# hitmouse.net
KiCad netlist of a schematic drawn in Altium Designer
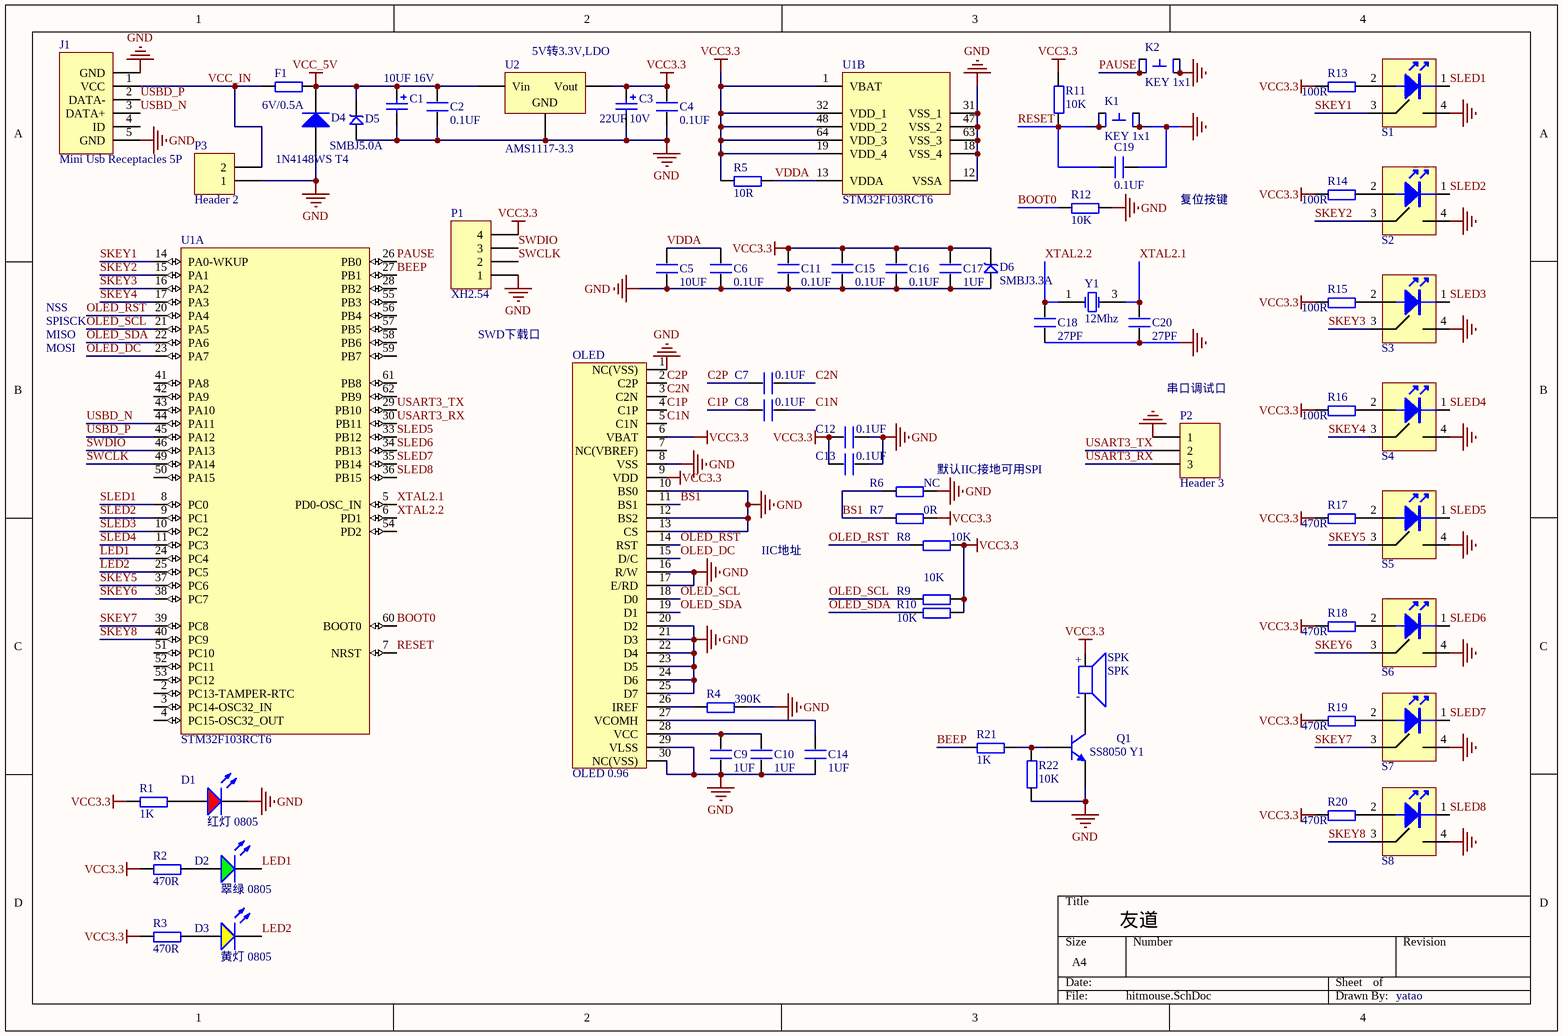
[diagram p0: hitmouse.SchDoc]

(export (version "E")
  (design (tool "Eeschema 10.0.6"))
  (components
    (comp (ref "*")
      (value "LOGO")
      (footprint "LOGO-14MM")
      (description "YOODAO-LOGO不焊接")
      (libsource (lib "yoodao") (part "LOGO"))
    )
    (comp (ref "C1")
      (value "10UF 16V")
      (footprint "CASE-A_3216")
      (description "钽电容A")
      (libsource (lib "yoodao") (part "C3216,A型钽电容"))
    )
    (comp (ref "C2")
      (value "0.1UF")
      (footprint "0805_C")
      (description "0805电容")
      (libsource (lib "") (part "C0805_1"))
    )
    (comp (ref "C3")
      (value "22UF 10V")
      (footprint "CASE-A_3216")
      (description "钽电容A")
      (libsource (lib "yoodao") (part "C3216,A型钽电容"))
    )
    (comp (ref "C4")
      (value "0.1UF")
      (footprint "0805_C")
      (description "0805电容")
      (libsource (lib "") (part "C0805_1"))
    )
    (comp (ref "C5")
      (value "10UF")
      (footprint "0805_C")
      (description "0805电容")
      (libsource (lib "yoodao") (part "C0805"))
    )
    (comp (ref "C6")
      (value "0.1UF")
      (footprint "0805_C")
      (description "0805电容")
      (libsource (lib "yoodao") (part "C0805"))
    )
    (comp (ref "C7")
      (value "0.1UF")
      (footprint "0805_C")
      (description "0805电容")
      (libsource (lib "yoodao") (part "C0805"))
    )
    (comp (ref "C8")
      (value "0.1UF")
      (footprint "0805_C")
      (description "0805电容")
      (libsource (lib "yoodao") (part "C0805"))
    )
    (comp (ref "C9")
      (value "1UF")
      (footprint "0805_C")
      (description "0805电容")
      (libsource (lib "yoodao") (part "C0805"))
    )
    (comp (ref "C10")
      (value "1UF")
      (footprint "0805_C")
      (description "0805电容")
      (libsource (lib "yoodao") (part "C0805"))
    )
    (comp (ref "C11")
      (value "0.1UF")
      (footprint "0805_C")
      (description "0805电容")
      (libsource (lib "yoodao") (part "C0805"))
    )
    (comp (ref "C12")
      (value "0.1UF")
      (footprint "0805_C")
      (description "0805电容")
      (libsource (lib "yoodao") (part "C0805"))
    )
    (comp (ref "C13")
      (value "0.1UF")
      (footprint "0805_C")
      (description "0805电容")
      (libsource (lib "yoodao") (part "C0805"))
    )
    (comp (ref "C14")
      (value "1UF")
      (footprint "0805_C")
      (description "0805电容")
      (libsource (lib "yoodao") (part "C0805"))
    )
    (comp (ref "C15")
      (value "0.1UF")
      (footprint "0805_C")
      (description "0805电容")
      (libsource (lib "yoodao") (part "C0805"))
    )
    (comp (ref "C16")
      (value "0.1UF")
      (footprint "0805_C")
      (description "0805电容")
      (libsource (lib "yoodao") (part "C0805"))
    )
    (comp (ref "C17")
      (value "1UF")
      (footprint "0805_C")
      (description "0805电容")
      (libsource (lib "yoodao") (part "C0805"))
    )
    (comp (ref "C18")
      (value "27PF")
      (footprint "0805_C")
      (description "0805电容")
      (libsource (lib "") (part "C0805_1"))
    )
    (comp (ref "C19")
      (value "0.1UF")
      (footprint "0805_C")
      (description "0805电容")
      (libsource (lib "") (part "C0805_1"))
    )
    (comp (ref "C20")
      (value "27PF")
      (footprint "0805_C")
      (description "0805电容")
      (libsource (lib "") (part "C0805_1"))
    )
    (comp (ref "D1")
      (value "红灯 0805")
      (footprint "0805_LED_S1")
      (description "发光二极管")
      (libsource (lib "yoodao") (part "0805 红灯"))
    )
    (comp (ref "D2")
      (value "翠绿 0805")
      (footprint "0805_LED_S1")
      (description "发光二极管")
      (libsource (lib "yoodao") (part "0805 翠绿"))
    )
    (comp (ref "D3")
      (value "黄灯 0805")
      (footprint "0805_LED_S1")
      (description "发光二极管")
      (libsource (lib "yoodao") (part "0805 黄灯"))
    )
    (comp (ref "D4")
      (value "1N4148WS T4")
      (footprint "SOD-323")
      (description "二极管")
      (libsource (lib "yoodao") (part "SOD-323 1N4148WS T4"))
    )
    (comp (ref "D5")
      (value "SMBJ5.0A")
      (footprint "SMBJ")
      (description "TVS")
      (libsource (lib "yoodao") (part "SMBJ"))
    )
    (comp (ref "D6")
      (value "SMBJ3.3A")
      (footprint "SMBJ")
      (description "TVS")
      (libsource (lib "yoodao") (part "SMBJ"))
    )
    (comp (ref "F1")
      (value "6V/0.5A")
      (footprint "0805_R")
      (description "0805贴片自恢复保险丝")
      (libsource (lib "yoodao") (part "R0805"))
    )
    (comp (ref "J1")
      (value "Mini Usb Receptacles 5P")
      (footprint "USB Micro MUP U513 F")
      (description "Micro USB 母座 5P 全贴有柱")
      (libsource (lib "yoodao") (part "USB Mini"))
    )
    (comp (ref "K1")
      (value "KEY 1x1")
      (footprint "BUT 6mm SMT")
      (description "贴片轻触按键6*6*5")
      (libsource (lib "yoodao") (part "KEY 1x1"))
    )
    (comp (ref "K2")
      (value "KEY 1x1")
      (footprint "BUT 6mm SMT")
      (description "贴片轻触按键6*6*5")
      (libsource (lib "yoodao") (part "KEY 1x1"))
    )
    (comp (ref "OLED")
      (value "OLED 0.96")
      (footprint "0.96_OLED")
      (description "0.96寸OLED贴片")
      (libsource (lib "yoodao") (part "OLED"))
    )
    (comp (ref "P1")
      (value "XH2.54")
      (footprint "XH2.54-LI-4P")
      (description "XH2.54 直/弯 带围墙")
      (fields (field (name "PUBLISHER") "Altium Limited"))
      (libsource (lib "yoodao") (part "XH2.54"))
    )
    (comp (ref "P2")
      (value "Header 3")
      (footprint "HDR1X3")
      (description "2.54直针")
      (fields (field (name "PUBLISHER") "Altium Limited"))
      (libsource (lib "yoodao") (part "Header 3"))
    )
    (comp (ref "P3")
      (value "Header 2")
      (footprint "HDR1X2")
      (description "Header, 2-Pin")
      (fields (field (name "PUBLISHER") "Altium Limited"))
      (libsource (lib "yoodao") (part "Header 2"))
    )
    (comp (ref "Q1")
      (value "SS8050 Y1")
      (footprint "SOT-23(SOT-23-3)")
      (description "NPN三极管SOT23")
      (libsource (lib "yoodao") (part "NPN"))
    )
    (comp (ref "R1")
      (value "1K")
      (footprint "0805_R")
      (description "0805贴片电阻")
      (libsource (lib "yoodao") (part "R0805"))
    )
    (comp (ref "R2")
      (value "470R")
      (footprint "0805_R")
      (description "0805贴片电阻")
      (libsource (lib "yoodao") (part "R0805"))
    )
    (comp (ref "R3")
      (value "470R")
      (footprint "0805_R")
      (description "0805贴片电阻")
      (libsource (lib "yoodao") (part "R0805"))
    )
    (comp (ref "R4")
      (value "390K")
      (footprint "0805_R")
      (description "0805贴片电阻")
      (libsource (lib "yoodao") (part "R0805"))
    )
    (comp (ref "R5")
      (value "10R")
      (footprint "0805_R")
      (description "0805贴片电阻")
      (libsource (lib "yoodao") (part "R0805"))
    )
    (comp (ref "R6")
      (value "NC")
      (footprint "0805_R")
      (description "0805贴片电阻")
      (libsource (lib "yoodao") (part "R0805"))
    )
    (comp (ref "R7")
      (value "0R")
      (footprint "0805_R")
      (description "0805贴片电阻")
      (libsource (lib "yoodao") (part "R0805"))
    )
    (comp (ref "R8")
      (value "10K")
      (footprint "0805_R")
      (description "0805贴片电阻")
      (libsource (lib "yoodao") (part "R0805"))
    )
    (comp (ref "R9")
      (value "10K")
      (footprint "0805_R")
      (description "0805贴片电阻")
      (libsource (lib "yoodao") (part "R0805"))
    )
    (comp (ref "R10")
      (value "10K")
      (footprint "0805_R")
      (description "0805贴片电阻")
      (libsource (lib "yoodao") (part "R0805"))
    )
    (comp (ref "R11")
      (value "10K")
      (footprint "0805_R")
      (description "0805贴片电阻")
      (libsource (lib "yoodao") (part "R0805"))
    )
    (comp (ref "R12")
      (value "10K")
      (footprint "0805_R")
      (description "0805贴片电阻")
      (libsource (lib "yoodao") (part "R0805"))
    )
    (comp (ref "R13")
      (value "100R")
      (footprint "0805_R")
      (description "0805贴片电阻")
      (libsource (lib "yoodao") (part "R0805"))
    )
    (comp (ref "R14")
      (value "100R")
      (footprint "0805_R")
      (description "0805贴片电阻")
      (libsource (lib "yoodao") (part "R0805"))
    )
    (comp (ref "R15")
      (value "100R")
      (footprint "0805_R")
      (description "0805贴片电阻")
      (libsource (lib "yoodao") (part "R0805"))
    )
    (comp (ref "R16")
      (value "100R")
      (footprint "0805_R")
      (description "0805贴片电阻")
      (libsource (lib "yoodao") (part "R0805"))
    )
    (comp (ref "R17")
      (value "470R")
      (footprint "0805_R")
      (description "0805贴片电阻")
      (libsource (lib "yoodao") (part "R0805"))
    )
    (comp (ref "R18")
      (value "470R")
      (footprint "0805_R")
      (description "0805贴片电阻")
      (libsource (lib "yoodao") (part "R0805"))
    )
    (comp (ref "R19")
      (value "470R")
      (footprint "0805_R")
      (description "0805贴片电阻")
      (libsource (lib "yoodao") (part "R0805"))
    )
    (comp (ref "R20")
      (value "470R")
      (footprint "0805_R")
      (description "0805贴片电阻")
      (libsource (lib "yoodao") (part "R0805"))
    )
    (comp (ref "R21")
      (value "1K")
      (footprint "0805_R")
      (description "0805贴片电阻")
      (libsource (lib "yoodao") (part "R0805"))
    )
    (comp (ref "R22")
      (value "10K")
      (footprint "0805_R")
      (description "0805贴片电阻")
      (libsource (lib "yoodao") (part "R0805"))
    )
    (comp (ref "S1")
      (value "12X12轻触带灯开关")
      (footprint "TSG010")
      (description "12X12按键带灯直插")
      (libsource (lib "yoodao") (part "LED开关12X12"))
    )
    (comp (ref "S2")
      (value "12X12轻触带灯开关")
      (footprint "TSG010")
      (description "12X12按键带灯直插")
      (libsource (lib "yoodao") (part "LED开关12X12"))
    )
    (comp (ref "S3")
      (value "12X12轻触带灯开关")
      (footprint "TSG010")
      (description "12X12按键带灯直插")
      (libsource (lib "yoodao") (part "LED开关12X12"))
    )
    (comp (ref "S4")
      (value "12X12轻触带灯开关")
      (footprint "TSG010")
      (description "12X12按键带灯直插")
      (libsource (lib "yoodao") (part "LED开关12X12"))
    )
    (comp (ref "S5")
      (value "12X12轻触带灯开关")
      (footprint "TSG010")
      (description "12X12按键带灯直插")
      (libsource (lib "yoodao") (part "LED开关12X12"))
    )
    (comp (ref "S6")
      (value "12X12轻触带灯开关")
      (footprint "TSG010")
      (description "12X12按键带灯直插")
      (libsource (lib "yoodao") (part "LED开关12X12"))
    )
    (comp (ref "S7")
      (value "12X12轻触带灯开关")
      (footprint "TSG010")
      (description "12X12按键带灯直插")
      (libsource (lib "yoodao") (part "LED开关12X12"))
    )
    (comp (ref "S8")
      (value "12X12轻触带灯开关")
      (footprint "TSG010")
      (description "12X12按键带灯直插")
      (libsource (lib "yoodao") (part "LED开关12X12"))
    )
    (comp (ref "SPK")
      (value "SPK")
      (footprint "SPAKER F12")
      (description "3.3V无源蜂鸣器，脚距7mm")
      (libsource (lib "yoodao") (part "SPK"))
    )
    (comp (ref "U1")
      (value "STM32F103RCT6")
      (footprint "LQFP-64_10x10x05P")
      (description "ARM")
      (libsource (lib "yoodao") (part "STM32F103RCT6"))
    )
    (comp (ref "U2")
      (value "AMS1117-3.3")
      (footprint "SOT-223")
      (description "低压差线性稳压(LDO)")
      (libsource (lib "yoodao") (part "SOT-223 AMS1117-3.3"))
    )
    (comp (ref "Y1")
      (value "12Mhz")
      (footprint "SMD-3225_4P")
      (description "2P无源贴片晶振3225")
      (libsource (lib "yoodao") (part "XTAL-3225_4P"))
    )
    (comp (ref "yatao")
      (value "NC")
      (footprint "Y-LOGO-8")
      (description "LOGO，不焊接")
      (libsource (lib "yoodao") (part "Yatao"))
    )
  )
  (nets
    (net (code "1") (name "/BEEP") (class "Default")
      (node (ref "R21") (pin "1") (pintype "passive"))
      (node (ref "U1") (pin "27") (pinfunction "PB1_27") (pintype "bidirectional"))
    )
    (net (code "2") (name "/BOOT0") (class "Default")
      (node (ref "R12") (pin "1") (pintype "passive"))
      (node (ref "U1") (pin "60") (pinfunction "BOOT0_60") (pintype "bidirectional"))
    )
    (net (code "3") (name "/BS1") (class "Default")
      (node (ref "OLED") (pin "11") (pinfunction "BS1_11") (pintype "passive"))
      (node (ref "R6") (pin "1") (pintype "passive"))
      (node (ref "R7") (pin "1") (pintype "passive"))
    )
    (net (code "4") (name "/C1N") (class "Default")
      (node (ref "C8") (pin "1") (pintype "passive"))
      (node (ref "OLED") (pin "5") (pinfunction "C1N_5") (pintype "passive"))
    )
    (net (code "5") (name "/C1P") (class "Default")
      (node (ref "C8") (pin "2") (pintype "passive"))
      (node (ref "OLED") (pin "4") (pinfunction "C1P_4") (pintype "passive"))
    )
    (net (code "6") (name "/C2N") (class "Default")
      (node (ref "C7") (pin "1") (pintype "passive"))
      (node (ref "OLED") (pin "3") (pinfunction "C2N_3") (pintype "passive"))
    )
    (net (code "7") (name "/C2P") (class "Default")
      (node (ref "C7") (pin "2") (pintype "passive"))
      (node (ref "OLED") (pin "2") (pinfunction "C2P_2") (pintype "passive"))
    )
    (net (code "8") (name "/LED1") (class "Default")
      (node (ref "D2") (pin "K") (pinfunction "K_K") (pintype "passive"))
      (node (ref "U1") (pin "24") (pinfunction "PC4_24") (pintype "bidirectional"))
    )
    (net (code "9") (name "/LED2") (class "Default")
      (node (ref "D3") (pin "K") (pinfunction "K_K") (pintype "passive"))
      (node (ref "U1") (pin "25") (pinfunction "PC5_25") (pintype "bidirectional"))
    )
    (net (code "10") (name "/OLED_DC") (class "Default")
      (node (ref "OLED") (pin "15") (pinfunction "D/C_15") (pintype "passive"))
      (node (ref "U1") (pin "23") (pinfunction "PA7_23") (pintype "bidirectional"))
    )
    (net (code "11") (name "/OLED_RST") (class "Default")
      (node (ref "OLED") (pin "14") (pinfunction "RST_14") (pintype "passive"))
      (node (ref "R8") (pin "1") (pintype "passive"))
      (node (ref "U1") (pin "20") (pinfunction "PA4_20") (pintype "bidirectional"))
    )
    (net (code "12") (name "/OLED_SCL") (class "Default")
      (node (ref "OLED") (pin "18") (pinfunction "D0_18") (pintype "passive"))
      (node (ref "R9") (pin "1") (pintype "passive"))
      (node (ref "U1") (pin "21") (pinfunction "PA5_21") (pintype "bidirectional"))
    )
    (net (code "13") (name "/OLED_SDA") (class "Default")
      (node (ref "OLED") (pin "19") (pinfunction "D1_19") (pintype "passive"))
      (node (ref "R10") (pin "1") (pintype "passive"))
      (node (ref "U1") (pin "22") (pinfunction "PA6_22") (pintype "bidirectional"))
    )
    (net (code "14") (name "/PAUSE") (class "Default")
      (node (ref "K2") (pin "1") (pinfunction "1_1") (pintype "passive"))
      (node (ref "K2") (pin "2") (pinfunction "2_2") (pintype "passive"))
      (node (ref "U1") (pin "26") (pinfunction "PB0_26") (pintype "bidirectional"))
    )
    (net (code "15") (name "/RESET") (class "Default")
      (node (ref "C19") (pin "2") (pintype "passive"))
      (node (ref "K1") (pin "1") (pinfunction "1_1") (pintype "passive"))
      (node (ref "K1") (pin "2") (pinfunction "2_2") (pintype "passive"))
      (node (ref "R11") (pin "1") (pintype "passive"))
      (node (ref "U1") (pin "7") (pinfunction "NRST_7") (pintype "bidirectional"))
    )
    (net (code "16") (name "/SKEY1") (class "Default")
      (node (ref "S1") (pin "3") (pinfunction "3_3") (pintype "passive"))
      (node (ref "U1") (pin "14") (pinfunction "PA0-WKUP_14") (pintype "bidirectional"))
    )
    (net (code "17") (name "/SKEY2") (class "Default")
      (node (ref "S2") (pin "3") (pinfunction "3_3") (pintype "passive"))
      (node (ref "U1") (pin "15") (pinfunction "PA1_15") (pintype "bidirectional"))
    )
    (net (code "18") (name "/SKEY3") (class "Default")
      (node (ref "S3") (pin "3") (pinfunction "3_3") (pintype "passive"))
      (node (ref "U1") (pin "16") (pinfunction "PA2_16") (pintype "bidirectional"))
    )
    (net (code "19") (name "/SKEY4") (class "Default")
      (node (ref "S4") (pin "3") (pinfunction "3_3") (pintype "passive"))
      (node (ref "U1") (pin "17") (pinfunction "PA3_17") (pintype "bidirectional"))
    )
    (net (code "20") (name "/SKEY5") (class "Default")
      (node (ref "S5") (pin "3") (pinfunction "3_3") (pintype "passive"))
      (node (ref "U1") (pin "37") (pinfunction "PC6_37") (pintype "bidirectional"))
    )
    (net (code "21") (name "/SKEY6") (class "Default")
      (node (ref "S6") (pin "3") (pinfunction "3_3") (pintype "passive"))
      (node (ref "U1") (pin "38") (pinfunction "PC7_38") (pintype "bidirectional"))
    )
    (net (code "22") (name "/SKEY7") (class "Default")
      (node (ref "S7") (pin "3") (pinfunction "3_3") (pintype "passive"))
      (node (ref "U1") (pin "39") (pinfunction "PC8_39") (pintype "bidirectional"))
    )
    (net (code "23") (name "/SKEY8") (class "Default")
      (node (ref "S8") (pin "3") (pinfunction "3_3") (pintype "passive"))
      (node (ref "U1") (pin "40") (pinfunction "PC9_40") (pintype "bidirectional"))
    )
    (net (code "24") (name "/SLED1") (class "Default")
      (node (ref "S1") (pin "1") (pinfunction "1_1") (pintype "passive"))
      (node (ref "U1") (pin "8") (pinfunction "PC0_8") (pintype "bidirectional"))
    )
    (net (code "25") (name "/SLED2") (class "Default")
      (node (ref "S2") (pin "1") (pinfunction "1_1") (pintype "passive"))
      (node (ref "U1") (pin "9") (pinfunction "PC1_9") (pintype "bidirectional"))
    )
    (net (code "26") (name "/SLED3") (class "Default")
      (node (ref "S3") (pin "1") (pinfunction "1_1") (pintype "passive"))
      (node (ref "U1") (pin "10") (pinfunction "PC2_10") (pintype "bidirectional"))
    )
    (net (code "27") (name "/SLED4") (class "Default")
      (node (ref "S4") (pin "1") (pinfunction "1_1") (pintype "passive"))
      (node (ref "U1") (pin "11") (pinfunction "PC3_11") (pintype "bidirectional"))
    )
    (net (code "28") (name "/SLED5") (class "Default")
      (node (ref "S5") (pin "1") (pinfunction "1_1") (pintype "passive"))
      (node (ref "U1") (pin "33") (pinfunction "PB12_33") (pintype "bidirectional"))
    )
    (net (code "29") (name "/SLED6") (class "Default")
      (node (ref "S6") (pin "1") (pinfunction "1_1") (pintype "passive"))
      (node (ref "U1") (pin "34") (pinfunction "PB13_34") (pintype "bidirectional"))
    )
    (net (code "30") (name "/SLED7") (class "Default")
      (node (ref "S7") (pin "1") (pinfunction "1_1") (pintype "passive"))
      (node (ref "U1") (pin "35") (pinfunction "PB14_35") (pintype "bidirectional"))
    )
    (net (code "31") (name "/SLED8") (class "Default")
      (node (ref "S8") (pin "1") (pinfunction "1_1") (pintype "passive"))
      (node (ref "U1") (pin "36") (pinfunction "PB15_36") (pintype "bidirectional"))
    )
    (net (code "32") (name "/SWCLK") (class "Default")
      (node (ref "P1") (pin "2") (pinfunction "2_2") (pintype "passive"))
      (node (ref "U1") (pin "49") (pinfunction "PA14_49") (pintype "bidirectional"))
    )
    (net (code "33") (name "/SWDIO") (class "Default")
      (node (ref "P1") (pin "3") (pinfunction "3_3") (pintype "passive"))
      (node (ref "U1") (pin "46") (pinfunction "PA13_46") (pintype "bidirectional"))
    )
    (net (code "34") (name "/USART3_RX") (class "Default")
      (node (ref "P2") (pin "3") (pinfunction "3_3") (pintype "passive"))
      (node (ref "U1") (pin "30") (pinfunction "PB11_30") (pintype "bidirectional"))
    )
    (net (code "35") (name "/USART3_TX") (class "Default")
      (node (ref "P2") (pin "2") (pinfunction "2_2") (pintype "passive"))
      (node (ref "U1") (pin "29") (pinfunction "PB10_29") (pintype "bidirectional"))
    )
    (net (code "36") (name "/USBD_N") (class "Default")
      (node (ref "J1") (pin "3") (pinfunction "DATA+_3") (pintype "passive"))
      (node (ref "U1") (pin "44") (pinfunction "PA11_44") (pintype "bidirectional"))
    )
    (net (code "37") (name "/USBD_P") (class "Default")
      (node (ref "J1") (pin "2") (pinfunction "DATA-_2") (pintype "passive"))
      (node (ref "U1") (pin "45") (pinfunction "PA12_45") (pintype "bidirectional"))
    )
    (net (code "38") (name "/VCC_IN") (class "Default")
      (node (ref "F1") (pin "1") (pintype "passive"))
      (node (ref "J1") (pin "1") (pinfunction "VCC_1") (pintype "passive"))
      (node (ref "P3") (pin "2") (pinfunction "2_2") (pintype "passive"))
    )
    (net (code "39") (name "/VDDA") (class "Default")
      (node (ref "C5") (pin "2") (pintype "passive"))
      (node (ref "C6") (pin "2") (pintype "passive"))
      (node (ref "R5") (pin "2") (pintype "passive"))
      (node (ref "U1") (pin "13") (pinfunction "VDDA_13") (pintype "power_in"))
    )
    (net (code "40") (name "/XTAL2.1") (class "Default")
      (node (ref "C20") (pin "1") (pintype "passive"))
      (node (ref "U1") (pin "5") (pinfunction "PD0-OSC_IN_5") (pintype "bidirectional"))
      (node (ref "Y1") (pin "3") (pinfunction "OSC2_3") (pintype "passive"))
    )
    (net (code "41") (name "/XTAL2.2") (class "Default")
      (node (ref "C18") (pin "1") (pintype "passive"))
      (node (ref "U1") (pin "6") (pinfunction "PD1_6") (pintype "bidirectional"))
      (node (ref "Y1") (pin "1") (pinfunction "OSC1_1") (pintype "passive"))
    )
    (net (code "42") (name "GND") (class "Default")
      (node (ref "C1") (pin "2") (pinfunction "2_2") (pintype "passive"))
      (node (ref "C10") (pin "1") (pintype "passive"))
      (node (ref "C11") (pin "1") (pintype "passive"))
      (node (ref "C12") (pin "1") (pintype "passive"))
      (node (ref "C13") (pin "1") (pintype "passive"))
      (node (ref "C14") (pin "1") (pintype "passive"))
      (node (ref "C15") (pin "1") (pintype "passive"))
      (node (ref "C16") (pin "1") (pintype "passive"))
      (node (ref "C17") (pin "1") (pintype "passive"))
      (node (ref "C18") (pin "2") (pintype "passive"))
      (node (ref "C19") (pin "1") (pintype "passive"))
      (node (ref "C2") (pin "1") (pintype "passive"))
      (node (ref "C20") (pin "2") (pintype "passive"))
      (node (ref "C3") (pin "2") (pinfunction "2_2") (pintype "passive"))
      (node (ref "C4") (pin "1") (pintype "passive"))
      (node (ref "C5") (pin "1") (pintype "passive"))
      (node (ref "C6") (pin "1") (pintype "passive"))
      (node (ref "C9") (pin "1") (pintype "passive"))
      (node (ref "D1") (pin "K") (pinfunction "K_K") (pintype "passive"))
      (node (ref "D4") (pin "1") (pinfunction "A_1") (pintype "passive"))
      (node (ref "D5") (pin "1") (pintype "passive"))
      (node (ref "D6") (pin "1") (pintype "passive"))
      (node (ref "J1") (pin "0") (pinfunction "GND_0") (pintype "passive"))
      (node (ref "J1") (pin "5") (pinfunction "GND_5") (pintype "passive"))
      (node (ref "K1") (pin "3") (pinfunction "3_3") (pintype "passive"))
      (node (ref "K1") (pin "4") (pinfunction "4_4") (pintype "passive"))
      (node (ref "K2") (pin "3") (pinfunction "3_3") (pintype "passive"))
      (node (ref "K2") (pin "4") (pinfunction "4_4") (pintype "passive"))
      (node (ref "OLED") (pin "1") (pinfunction "NC(VSS)_1") (pintype "passive"))
      (node (ref "OLED") (pin "10") (pinfunction "BS0_10") (pintype "passive"))
      (node (ref "OLED") (pin "12") (pinfunction "BS2_12") (pintype "passive"))
      (node (ref "OLED") (pin "13") (pinfunction "CS_13") (pintype "passive"))
      (node (ref "OLED") (pin "16") (pinfunction "R/W_16") (pintype "passive"))
      (node (ref "OLED") (pin "17") (pinfunction "E/RD_17") (pintype "passive"))
      (node (ref "OLED") (pin "20") (pinfunction "D2_20") (pintype "passive"))
      (node (ref "OLED") (pin "21") (pinfunction "D3_21") (pintype "passive"))
      (node (ref "OLED") (pin "22") (pinfunction "D4_22") (pintype "passive"))
      (node (ref "OLED") (pin "23") (pinfunction "D5_23") (pintype "passive"))
      (node (ref "OLED") (pin "24") (pinfunction "D6_24") (pintype "passive"))
      (node (ref "OLED") (pin "25") (pinfunction "D7_25") (pintype "passive"))
      (node (ref "OLED") (pin "29") (pinfunction "VLSS_29") (pintype "passive"))
      (node (ref "OLED") (pin "30") (pinfunction "NC(VSS)_30") (pintype "passive"))
      (node (ref "OLED") (pin "8") (pinfunction "VSS_8") (pintype "passive"))
      (node (ref "P1") (pin "1") (pinfunction "1_1") (pintype "passive"))
      (node (ref "P2") (pin "1") (pinfunction "1_1") (pintype "passive"))
      (node (ref "P3") (pin "1") (pinfunction "1_1") (pintype "passive"))
      (node (ref "Q1") (pin "2") (pinfunction "E_2") (pintype "passive"))
      (node (ref "R12") (pin "2") (pintype "passive"))
      (node (ref "R22") (pin "1") (pintype "passive"))
      (node (ref "R4") (pin "2") (pintype "passive"))
      (node (ref "R6") (pin "2") (pintype "passive"))
      (node (ref "S1") (pin "4") (pinfunction "4_4") (pintype "passive"))
      (node (ref "S2") (pin "4") (pinfunction "4_4") (pintype "passive"))
      (node (ref "S3") (pin "4") (pinfunction "4_4") (pintype "passive"))
      (node (ref "S4") (pin "4") (pinfunction "4_4") (pintype "passive"))
      (node (ref "S5") (pin "4") (pinfunction "4_4") (pintype "passive"))
      (node (ref "S6") (pin "4") (pinfunction "4_4") (pintype "passive"))
      (node (ref "S7") (pin "4") (pinfunction "4_4") (pintype "passive"))
      (node (ref "S8") (pin "4") (pinfunction "4_4") (pintype "passive"))
      (node (ref "U1") (pin "12") (pinfunction "VSSA_12") (pintype "power_in"))
      (node (ref "U1") (pin "18") (pinfunction "VSS_4_18") (pintype "power_in"))
      (node (ref "U1") (pin "31") (pinfunction "VSS_1_31") (pintype "power_in"))
      (node (ref "U1") (pin "47") (pinfunction "VSS_2_47") (pintype "power_in"))
      (node (ref "U1") (pin "63") (pinfunction "VSS_3_63") (pintype "power_in"))
      (node (ref "U2") (pin "1") (pinfunction "GND_1") (pintype "passive"))
    )
    (net (code "43") (name "Net-(D1-PadA)") (class "Default")
      (node (ref "D1") (pin "A") (pinfunction "A_A") (pintype "passive"))
      (node (ref "R1") (pin "2") (pintype "passive"))
    )
    (net (code "44") (name "Net-(D2-PadA)") (class "Default")
      (node (ref "D2") (pin "A") (pinfunction "A_A") (pintype "passive"))
      (node (ref "R2") (pin "2") (pintype "passive"))
    )
    (net (code "45") (name "Net-(D3-PadA)") (class "Default")
      (node (ref "D3") (pin "A") (pinfunction "A_A") (pintype "passive"))
      (node (ref "R3") (pin "2") (pintype "passive"))
    )
    (net (code "46") (name "Net-(OLED-IREF)") (class "Default")
      (node (ref "OLED") (pin "26") (pinfunction "IREF_26") (pintype "passive"))
      (node (ref "R4") (pin "1") (pintype "passive"))
    )
    (net (code "47") (name "Net-(OLED-VCC)") (class "Default")
      (node (ref "C10") (pin "2") (pintype "passive"))
      (node (ref "C9") (pin "2") (pintype "passive"))
      (node (ref "OLED") (pin "28") (pinfunction "VCC_28") (pintype "passive"))
    )
    (net (code "48") (name "Net-(OLED-VCOMH)") (class "Default")
      (node (ref "C14") (pin "2") (pintype "passive"))
      (node (ref "OLED") (pin "27") (pinfunction "VCOMH_27") (pintype "passive"))
    )
    (net (code "49") (name "Net-(Q1-B)") (class "Default")
      (node (ref "Q1") (pin "1") (pinfunction "B_1") (pintype "passive"))
      (node (ref "R21") (pin "2") (pintype "passive"))
      (node (ref "R22") (pin "2") (pintype "passive"))
    )
    (net (code "50") (name "Net-(Q1-C)") (class "Default")
      (node (ref "Q1") (pin "3") (pinfunction "C_3") (pintype "passive"))
      (node (ref "SPK") (pin "2") (pinfunction "2_2") (pintype "passive"))
    )
    (net (code "51") (name "Net-(R13-Pad2)") (class "Default")
      (node (ref "R13") (pin "2") (pintype "passive"))
      (node (ref "S1") (pin "2") (pinfunction "2_2") (pintype "passive"))
    )
    (net (code "52") (name "Net-(R14-Pad2)") (class "Default")
      (node (ref "R14") (pin "2") (pintype "passive"))
      (node (ref "S2") (pin "2") (pinfunction "2_2") (pintype "passive"))
    )
    (net (code "53") (name "Net-(R15-Pad2)") (class "Default")
      (node (ref "R15") (pin "2") (pintype "passive"))
      (node (ref "S3") (pin "2") (pinfunction "2_2") (pintype "passive"))
    )
    (net (code "54") (name "Net-(R16-Pad2)") (class "Default")
      (node (ref "R16") (pin "2") (pintype "passive"))
      (node (ref "S4") (pin "2") (pinfunction "2_2") (pintype "passive"))
    )
    (net (code "55") (name "Net-(R17-Pad2)") (class "Default")
      (node (ref "R17") (pin "2") (pintype "passive"))
      (node (ref "S5") (pin "2") (pinfunction "2_2") (pintype "passive"))
    )
    (net (code "56") (name "Net-(R18-Pad2)") (class "Default")
      (node (ref "R18") (pin "2") (pintype "passive"))
      (node (ref "S6") (pin "2") (pinfunction "2_2") (pintype "passive"))
    )
    (net (code "57") (name "Net-(R19-Pad2)") (class "Default")
      (node (ref "R19") (pin "2") (pintype "passive"))
      (node (ref "S7") (pin "2") (pinfunction "2_2") (pintype "passive"))
    )
    (net (code "58") (name "Net-(R20-Pad2)") (class "Default")
      (node (ref "R20") (pin "2") (pintype "passive"))
      (node (ref "S8") (pin "2") (pinfunction "2_2") (pintype "passive"))
    )
    (net (code "59") (name "VCC3.3") (class "Default")
      (node (ref "C11") (pin "2") (pintype "passive"))
      (node (ref "C12") (pin "2") (pintype "passive"))
      (node (ref "C13") (pin "2") (pintype "passive"))
      (node (ref "C15") (pin "2") (pintype "passive"))
      (node (ref "C16") (pin "2") (pintype "passive"))
      (node (ref "C17") (pin "2") (pintype "passive"))
      (node (ref "C3") (pin "1") (pinfunction "1_1") (pintype "passive"))
      (node (ref "C4") (pin "2") (pintype "passive"))
      (node (ref "D6") (pin "2") (pintype "passive"))
      (node (ref "OLED") (pin "6") (pinfunction "VBAT_6") (pintype "passive"))
      (node (ref "OLED") (pin "9") (pinfunction "VDD_9") (pintype "passive"))
      (node (ref "P1") (pin "4") (pinfunction "4_4") (pintype "passive"))
      (node (ref "R1") (pin "1") (pintype "passive"))
      (node (ref "R10") (pin "2") (pintype "passive"))
      (node (ref "R11") (pin "2") (pintype "passive"))
      (node (ref "R13") (pin "1") (pintype "passive"))
      (node (ref "R14") (pin "1") (pintype "passive"))
      (node (ref "R15") (pin "1") (pintype "passive"))
      (node (ref "R16") (pin "1") (pintype "passive"))
      (node (ref "R17") (pin "1") (pintype "passive"))
      (node (ref "R18") (pin "1") (pintype "passive"))
      (node (ref "R19") (pin "1") (pintype "passive"))
      (node (ref "R2") (pin "1") (pintype "passive"))
      (node (ref "R20") (pin "1") (pintype "passive"))
      (node (ref "R3") (pin "1") (pintype "passive"))
      (node (ref "R5") (pin "1") (pintype "passive"))
      (node (ref "R7") (pin "2") (pintype "passive"))
      (node (ref "R8") (pin "2") (pintype "passive"))
      (node (ref "R9") (pin "2") (pintype "passive"))
      (node (ref "SPK") (pin "1") (pinfunction "1_1") (pintype "passive"))
      (node (ref "U1") (pin "1") (pinfunction "VBAT_1") (pintype "power_in"))
      (node (ref "U1") (pin "19") (pinfunction "VDD_4_19") (pintype "power_in"))
      (node (ref "U1") (pin "32") (pinfunction "VDD_1_32") (pintype "power_in"))
      (node (ref "U1") (pin "48") (pinfunction "VDD_2_48") (pintype "power_in"))
      (node (ref "U1") (pin "64") (pinfunction "VDD_3_64") (pintype "power_in"))
      (node (ref "U2") (pin "2") (pinfunction "Vout_2") (pintype "passive"))
    )
    (net (code "60") (name "VCC_5V") (class "Default")
      (node (ref "C1") (pin "1") (pinfunction "1_1") (pintype "passive"))
      (node (ref "C2") (pin "2") (pintype "passive"))
      (node (ref "D4") (pin "2") (pinfunction "K_2") (pintype "passive"))
      (node (ref "D5") (pin "2") (pintype "passive"))
      (node (ref "F1") (pin "2") (pintype "passive"))
      (node (ref "U2") (pin "3") (pinfunction "Vin_3") (pintype "passive"))
    )
    (net (code "61") (name "unconnected-(J1-ID-Pad4)") (class "Default")
      (node (ref "J1") (pin "4") (pinfunction "ID_4") (pintype "passive"))
    )
    (net (code "62") (name "unconnected-(OLED-NC(VBREF)-Pad7)") (class "Default")
      (node (ref "OLED") (pin "7") (pinfunction "NC(VBREF)_7") (pintype "passive"))
    )
    (net (code "63") (name "unconnected-(U1A-PA8-Pad41)") (class "Default")
      (node (ref "U1") (pin "41") (pinfunction "PA8_41") (pintype "bidirectional"))
    )
    (net (code "64") (name "unconnected-(U1A-PA9-Pad42)") (class "Default")
      (node (ref "U1") (pin "42") (pinfunction "PA9_42") (pintype "bidirectional"))
    )
    (net (code "65") (name "unconnected-(U1A-PA10-Pad43)") (class "Default")
      (node (ref "U1") (pin "43") (pinfunction "PA10_43") (pintype "bidirectional"))
    )
    (net (code "66") (name "unconnected-(U1A-PA15-Pad50)") (class "Default")
      (node (ref "U1") (pin "50") (pinfunction "PA15_50") (pintype "bidirectional"))
    )
    (net (code "67") (name "unconnected-(U1A-PB2-Pad28)") (class "Default")
      (node (ref "U1") (pin "28") (pinfunction "PB2_28") (pintype "bidirectional"))
    )
    (net (code "68") (name "unconnected-(U1A-PB3-Pad55)") (class "Default")
      (node (ref "U1") (pin "55") (pinfunction "PB3_55") (pintype "bidirectional"))
    )
    (net (code "69") (name "unconnected-(U1A-PB4-Pad56)") (class "Default")
      (node (ref "U1") (pin "56") (pinfunction "PB4_56") (pintype "bidirectional"))
    )
    (net (code "70") (name "unconnected-(U1A-PB5-Pad57)") (class "Default")
      (node (ref "U1") (pin "57") (pinfunction "PB5_57") (pintype "bidirectional"))
    )
    (net (code "71") (name "unconnected-(U1A-PB6-Pad58)") (class "Default")
      (node (ref "U1") (pin "58") (pinfunction "PB6_58") (pintype "bidirectional"))
    )
    (net (code "72") (name "unconnected-(U1A-PB7-Pad59)") (class "Default")
      (node (ref "U1") (pin "59") (pinfunction "PB7_59") (pintype "bidirectional"))
    )
    (net (code "73") (name "unconnected-(U1A-PB8-Pad61)") (class "Default")
      (node (ref "U1") (pin "61") (pinfunction "PB8_61") (pintype "bidirectional"))
    )
    (net (code "74") (name "unconnected-(U1A-PB9-Pad62)") (class "Default")
      (node (ref "U1") (pin "62") (pinfunction "PB9_62") (pintype "bidirectional"))
    )
    (net (code "75") (name "unconnected-(U1A-PC10-Pad51)") (class "Default")
      (node (ref "U1") (pin "51") (pinfunction "PC10_51") (pintype "bidirectional"))
    )
    (net (code "76") (name "unconnected-(U1A-PC11-Pad52)") (class "Default")
      (node (ref "U1") (pin "52") (pinfunction "PC11_52") (pintype "bidirectional"))
    )
    (net (code "77") (name "unconnected-(U1A-PC12-Pad53)") (class "Default")
      (node (ref "U1") (pin "53") (pinfunction "PC12_53") (pintype "bidirectional"))
    )
    (net (code "78") (name "unconnected-(U1A-PC13-TAMPER-RTC-Pad2)") (class "Default")
      (node (ref "U1") (pin "2") (pinfunction "PC13-TAMPER-RTC_2") (pintype "bidirectional"))
    )
    (net (code "79") (name "unconnected-(U1A-PC14-OSC32_IN-Pad3)") (class "Default")
      (node (ref "U1") (pin "3") (pinfunction "PC14-OSC32_IN_3") (pintype "bidirectional"))
    )
    (net (code "80") (name "unconnected-(U1A-PC15-OSC32_OUT-Pad4)") (class "Default")
      (node (ref "U1") (pin "4") (pinfunction "PC15-OSC32_OUT_4") (pintype "bidirectional"))
    )
    (net (code "81") (name "unconnected-(U1A-PD2-Pad54)") (class "Default")
      (node (ref "U1") (pin "54") (pinfunction "PD2_54") (pintype "bidirectional"))
    )
  )
)
